# MIXR_UI_-_Buttons.net
KiCad netlist of a schematic drawn in Altium Designer
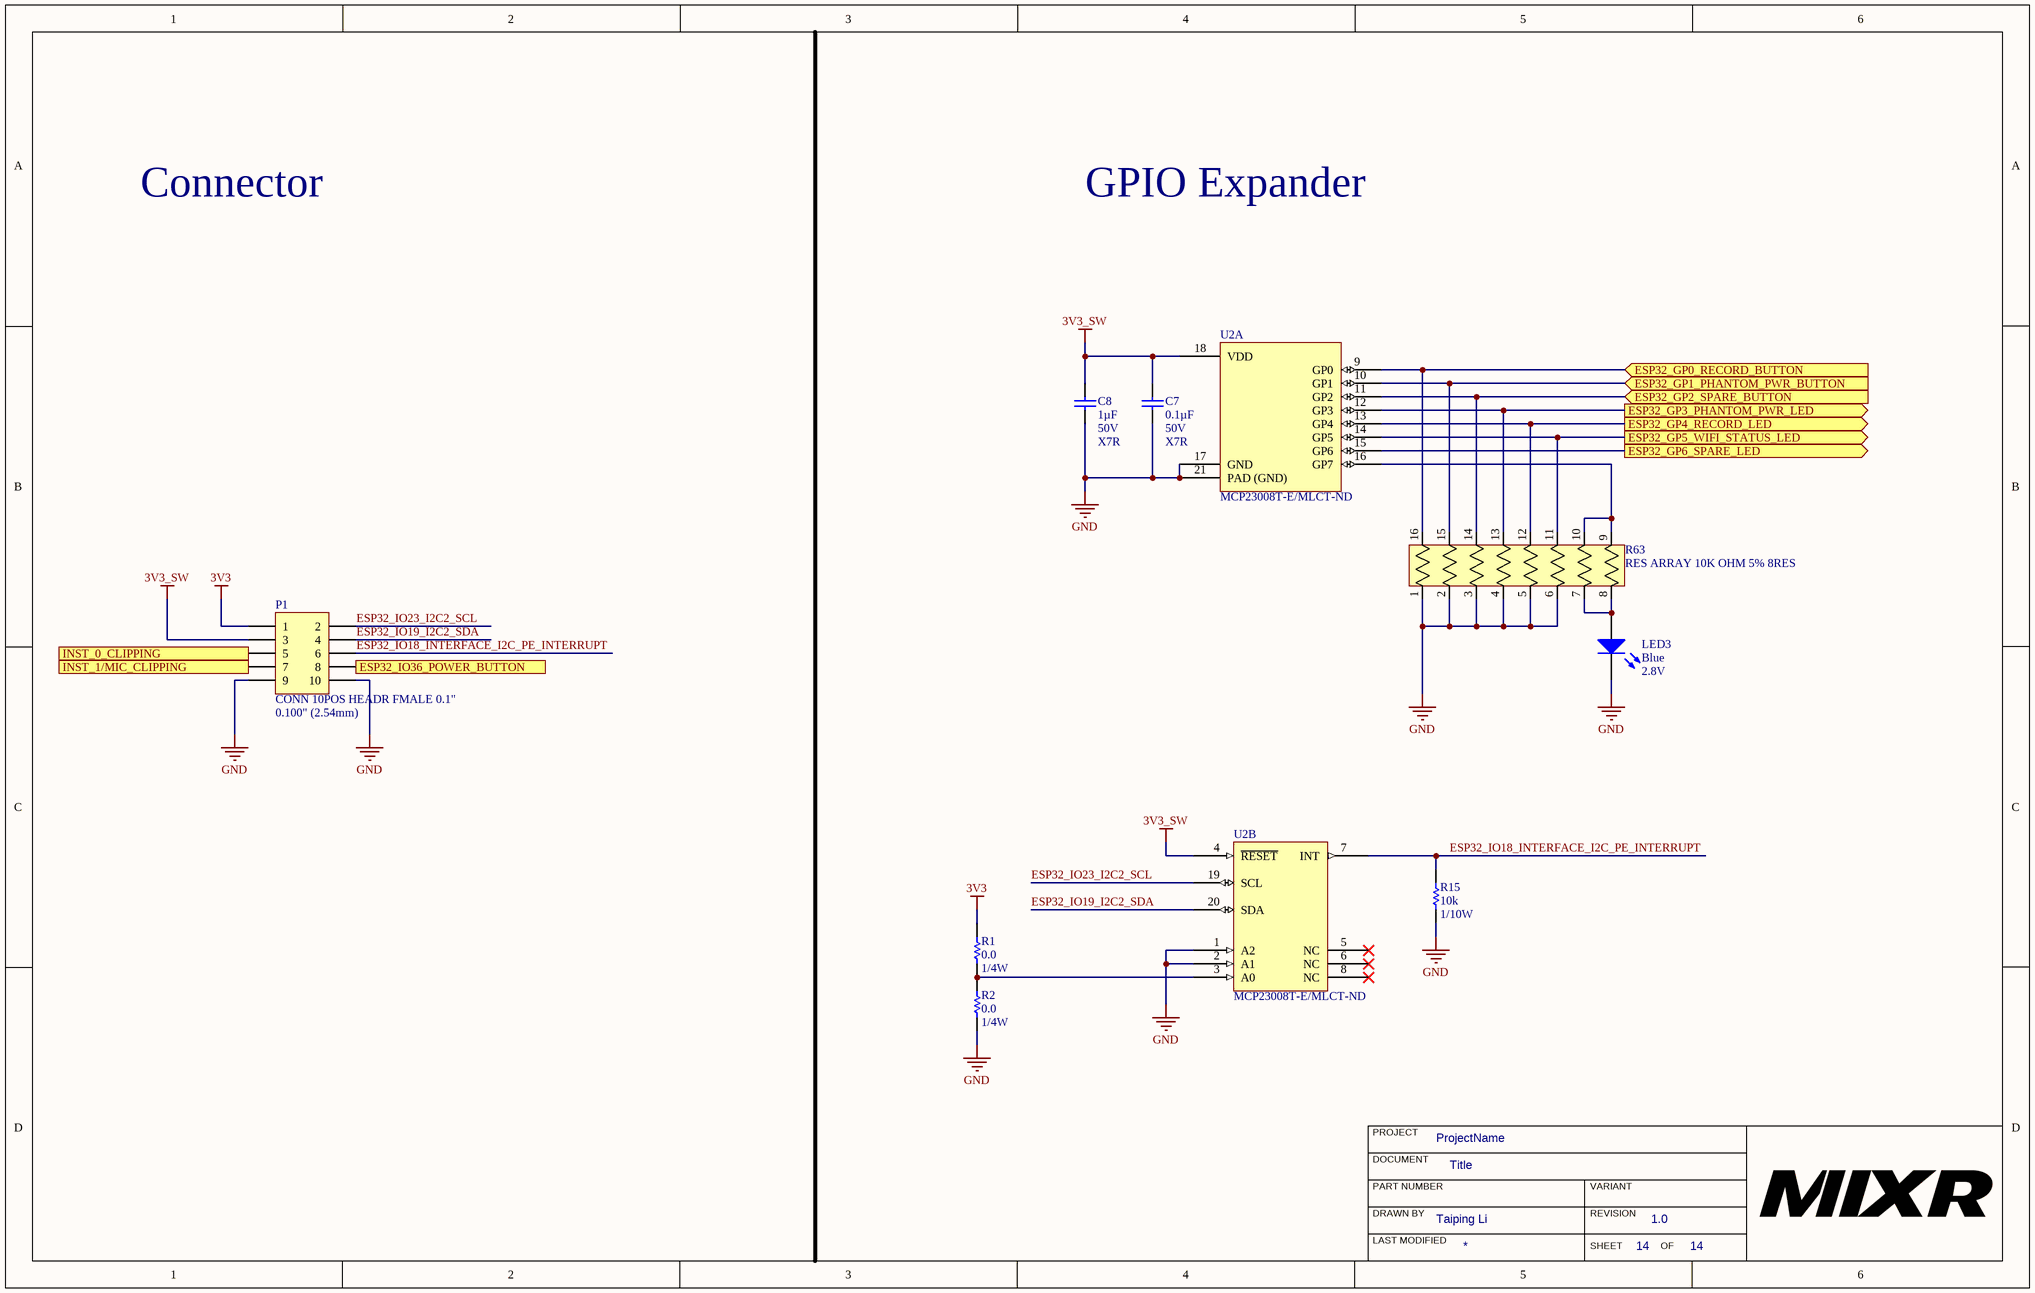
[diagram p0: MIXR UI - Buttons.SchDoc]

(export (version "E")
  (design (tool "Eeschema 10.0.6"))
  (components
    (comp (ref "C7")
      (value "CAP CER 0.1UF 50V 10% X7R 0603")
      (footprint "CAP, 0603")
      (description "0.10µF ±10% 50V Ceramic Capacitor X7R 0603 (1608 Metric)")
      (fields
        (field (name "TOLERANCE") "±10%")
        (field (name "CAPACITANCE") "0.1µF")
        (field (name "VOLTAGE") "50V")
        (field (name "TEMPERATURE COEFFICIENT") "X7R")
      )
      (libsource (lib "Schematic Diagrams") (part "CAP CER 0.1UF 50V 10% X7R 0603"))
    )
    (comp (ref "C8")
      (value "CAP CER 1UF 50V 10% X7R 0603")
      (footprint "CAP, 0603")
      (description "1µF ±10% 50V Ceramic Capacitor X7R 0603 (1608 Metric)")
      (fields
        (field (name "TOLERANCE") "±10%")
        (field (name "CAPACITANCE") "1µF")
        (field (name "VOLTAGE") "50V")
        (field (name "TEMPERATURE COEFFICIENT") "X7R")
      )
      (libsource (lib "Schematic Diagrams") (part "CAP CER 1UF 50V 10% X7R 0603"))
    )
    (comp (ref "LED3")
      (value "LED BLUE CLEAR 2.8V 0603")
      (footprint "LED_0603")
      (description "Blue 470nm LED Indication - Discrete 2.8V 0603 (1608 Metric)")
      (fields (field (name "COLOR") "Blue") (field (name "VOLTAGE - FORWARD (VF) (TYP)") "2.8V"))
      (libsource (lib "Schematic Diagrams") (part "LED BLUE CLEAR 2.8V 0603"))
    )
    (comp (ref "P1")
      (value "CONN 10POS HEADR FMALE 0.1\"")
      (footprint "CONN ,10 POS Header 0.100\"")
      (description "10 Position Header Connector 0.100\" (2.54mm) Through Hole, Right Angle Gold")
      (fields (field (name "PITCH - MATING") "0.100\" (2.54mm)"))
      (libsource (lib "Schematic Diagrams") (part "CONN 10POS HEADR FMALE 0.1{dblquote}"))
    )
    (comp (ref "R1")
      (value "RES 0.0 OHM 1/4W 0603")
      (footprint "RES, 0603")
      (description "RES SMD 0.0 OHM JUMPER 1/4W 0603")
      (fields (field (name "RESISTANCE") "0.0") (field (name "POWER (WATTS)") "1/4W"))
      (libsource (lib "Schematic Diagrams") (part "RES 0.0 OHM 1/4W 0603"))
    )
    (comp (ref "R2")
      (value "RES 0.0 OHM 1/4W 0603")
      (footprint "RES, 0603")
      (description "RES SMD 0.0 OHM JUMPER 1/4W 0603")
      (fields (field (name "RESISTANCE") "0.0") (field (name "POWER (WATTS)") "1/4W"))
      (libsource (lib "Schematic Diagrams") (part "RES 0.0 OHM 1/4W 0603"))
    )
    (comp (ref "R15")
      (value "RES 10K OHM 1% 1/10W 0603")
      (footprint "RES, 0603")
      (description "RES SMD 10K OHM 1% 1/10W 0603")
      (fields
        (field (name "TOLERANCE") "±1%")
        (field (name "RESISTANCE") "10k")
        (field (name "POWER") "1/10W")
      )
      (libsource (lib "Schematic Diagrams") (part "RES 10K OHM 1% 1/10W 0603"))
    )
    (comp (ref "R63")
      (value "RES ARRAY 10K OHM 5% 8RES")
      (footprint "RES ARRAY, 8 POS 1506")
      (description "RES ARRAY SMD 10K 5% 62.5mW 1506")
      (fields
        (field (name "MANUFACTURER_PART_NUMBER") "EXB-2HV103JV")
        (field (name "MANUFACTURER") "Panasonic Electronic Components")
        (field (name "COPYRIGHT") "Copyright (C) 2015 Accelerated Designs. All rights reserved")
      )
      (libsource (lib "Schematic Diagrams") (part "RES ARRAY 10K OHM 5% 8RES EXB-2HV103JV"))
    )
    (comp (ref "U2")
      (value "MCP23008")
      (footprint "QFN50P400X400X100_HS-21M")
      (description "I/O Expander 8 I²C 1.7MHz 20-QFN-EP (4x4)")
      (fields (field (name "SUPPLIER PART NUMBER 1") "MCP23008T-E/MLCT-ND"))
      (libsource (lib "Schematic Diagrams") (part "IC I/O EXPANDER I2C 8CH 20 QFN"))
    )
  )
  (nets
    (net (code "1") (name "/ESP32_GP0_RECORD_BUTTON") (class "Default")
      (node (ref "R63") (pin "16") (pinfunction "16_16") (pintype "passive"))
      (node (ref "U2") (pin "9") (pinfunction "GP0_9") (pintype "bidirectional"))
    )
    (net (code "2") (name "/ESP32_GP1_PHANTOM_PWR_BUTTON") (class "Default")
      (node (ref "R63") (pin "15") (pinfunction "15_15") (pintype "passive"))
      (node (ref "U2") (pin "10") (pinfunction "GP1_10") (pintype "bidirectional"))
    )
    (net (code "3") (name "/ESP32_GP2_SPARE_BUTTON") (class "Default")
      (node (ref "R63") (pin "14") (pinfunction "14_14") (pintype "passive"))
      (node (ref "U2") (pin "11") (pinfunction "GP2_11") (pintype "bidirectional"))
    )
    (net (code "4") (name "/ESP32_GP3_PHANTOM_PWR_LED") (class "Default")
      (node (ref "R63") (pin "13") (pinfunction "13_13") (pintype "passive"))
      (node (ref "U2") (pin "12") (pinfunction "GP3_12") (pintype "bidirectional"))
    )
    (net (code "5") (name "/ESP32_GP4_RECORD_LED") (class "Default")
      (node (ref "R63") (pin "12") (pinfunction "12_12") (pintype "passive"))
      (node (ref "U2") (pin "13") (pinfunction "GP4_13") (pintype "bidirectional"))
    )
    (net (code "6") (name "/ESP32_GP5_WIFI_STATUS_LED") (class "Default")
      (node (ref "R63") (pin "11") (pinfunction "11_11") (pintype "passive"))
      (node (ref "U2") (pin "14") (pinfunction "GP5_14") (pintype "bidirectional"))
    )
    (net (code "7") (name "/ESP32_GP6_SPARE_LED") (class "Default")
      (node (ref "U2") (pin "15") (pinfunction "GP6_15") (pintype "bidirectional"))
    )
    (net (code "8") (name "/ESP32_IO18_INTERFACE_I2C_PE_INTERRUPT") (class "Default")
      (node (ref "P1") (pin "6") (pinfunction "6_6") (pintype "passive"))
      (node (ref "R15") (pin "1") (pinfunction "1_1") (pintype "passive"))
      (node (ref "U2") (pin "7") (pinfunction "INT_7") (pintype "output"))
    )
    (net (code "9") (name "/ESP32_IO19_I2C2_SDA") (class "Default")
      (node (ref "P1") (pin "4") (pinfunction "4_4") (pintype "passive"))
      (node (ref "U2") (pin "20") (pinfunction "SDA_20") (pintype "bidirectional"))
    )
    (net (code "10") (name "/ESP32_IO23_I2C2_SCL") (class "Default")
      (node (ref "P1") (pin "2") (pinfunction "2_2") (pintype "passive"))
      (node (ref "U2") (pin "19") (pinfunction "SCL_19") (pintype "bidirectional"))
    )
    (net (code "11") (name "/ESP32_IO36_POWER_BUTTON") (class "Default")
      (node (ref "P1") (pin "8") (pinfunction "8_8") (pintype "passive"))
    )
    (net (code "12") (name "/INST_0_CLIPPING") (class "Default")
      (node (ref "P1") (pin "5") (pinfunction "5_5") (pintype "passive"))
    )
    (net (code "13") (name "/INST_1{slash}MIC_CLIPPING") (class "Default")
      (node (ref "P1") (pin "7") (pinfunction "7_7") (pintype "passive"))
    )
    (net (code "14") (name "3V3") (class "Default")
      (node (ref "P1") (pin "1") (pinfunction "1_1") (pintype "passive"))
      (node (ref "R1") (pin "1") (pinfunction "1_1") (pintype "passive"))
    )
    (net (code "15") (name "3V3_SW") (class "Default")
      (node (ref "C7") (pin "1") (pinfunction "1_1") (pintype "passive"))
      (node (ref "C8") (pin "1") (pinfunction "1_1") (pintype "passive"))
      (node (ref "P1") (pin "3") (pinfunction "3_3") (pintype "passive"))
      (node (ref "U2") (pin "18") (pinfunction "VDD_18") (pintype "power_in"))
      (node (ref "U2") (pin "4") (pinfunction "~{RESET}_4") (pintype "input"))
    )
    (net (code "16") (name "GND") (class "Default")
      (node (ref "C7") (pin "2") (pinfunction "2_2") (pintype "passive"))
      (node (ref "C8") (pin "2") (pinfunction "2_2") (pintype "passive"))
      (node (ref "LED3") (pin "2") (pinfunction "K_2") (pintype "passive"))
      (node (ref "P1") (pin "10") (pinfunction "10_10") (pintype "passive"))
      (node (ref "P1") (pin "9") (pinfunction "9_9") (pintype "passive"))
      (node (ref "R15") (pin "2") (pinfunction "2_2") (pintype "passive"))
      (node (ref "R2") (pin "2") (pinfunction "2_2") (pintype "passive"))
      (node (ref "R63") (pin "1") (pinfunction "1_1") (pintype "passive"))
      (node (ref "R63") (pin "2") (pinfunction "2_2") (pintype "passive"))
      (node (ref "R63") (pin "3") (pinfunction "3_3") (pintype "passive"))
      (node (ref "R63") (pin "4") (pinfunction "4_4") (pintype "passive"))
      (node (ref "R63") (pin "5") (pinfunction "5_5") (pintype "passive"))
      (node (ref "R63") (pin "6") (pinfunction "6_6") (pintype "passive"))
      (node (ref "U2") (pin "1") (pinfunction "A2_1") (pintype "input"))
      (node (ref "U2") (pin "17") (pinfunction "GND_17") (pintype "power_in"))
      (node (ref "U2") (pin "2") (pinfunction "A1_2") (pintype "input"))
      (node (ref "U2") (pin "21") (pinfunction "PAD_(GND)_21") (pintype "power_in"))
    )
    (net (code "17") (name "Net-(LED3-A)") (class "Default")
      (node (ref "LED3") (pin "1") (pinfunction "A_1") (pintype "passive"))
      (node (ref "R63") (pin "7") (pinfunction "7_7") (pintype "passive"))
      (node (ref "R63") (pin "8") (pinfunction "8_8") (pintype "passive"))
    )
    (net (code "18") (name "Net-(U2A-GP7)") (class "Default")
      (node (ref "R63") (pin "10") (pinfunction "10_10") (pintype "passive"))
      (node (ref "R63") (pin "9") (pinfunction "9_9") (pintype "passive"))
      (node (ref "U2") (pin "16") (pinfunction "GP7_16") (pintype "bidirectional"))
    )
    (net (code "19") (name "Net-(U2B-A0)") (class "Default")
      (node (ref "R1") (pin "2") (pinfunction "2_2") (pintype "passive"))
      (node (ref "R2") (pin "1") (pinfunction "1_1") (pintype "passive"))
      (node (ref "U2") (pin "3") (pinfunction "A0_3") (pintype "input"))
    )
    (net (code "20") (name "unconnected-(U2B-NC-Pad5)") (class "Default")
      (node (ref "U2") (pin "5") (pinfunction "NC_5") (pintype "passive+no_connect"))
    )
    (net (code "21") (name "unconnected-(U2B-NC-Pad6)") (class "Default")
      (node (ref "U2") (pin "6") (pinfunction "NC_6") (pintype "passive+no_connect"))
    )
    (net (code "22") (name "unconnected-(U2B-NC-Pad8)") (class "Default")
      (node (ref "U2") (pin "8") (pinfunction "NC_8") (pintype "passive+no_connect"))
    )
  )
)
